# ST_LINK_V3E.net
KiCad netlist of a schematic drawn in Altium Designer
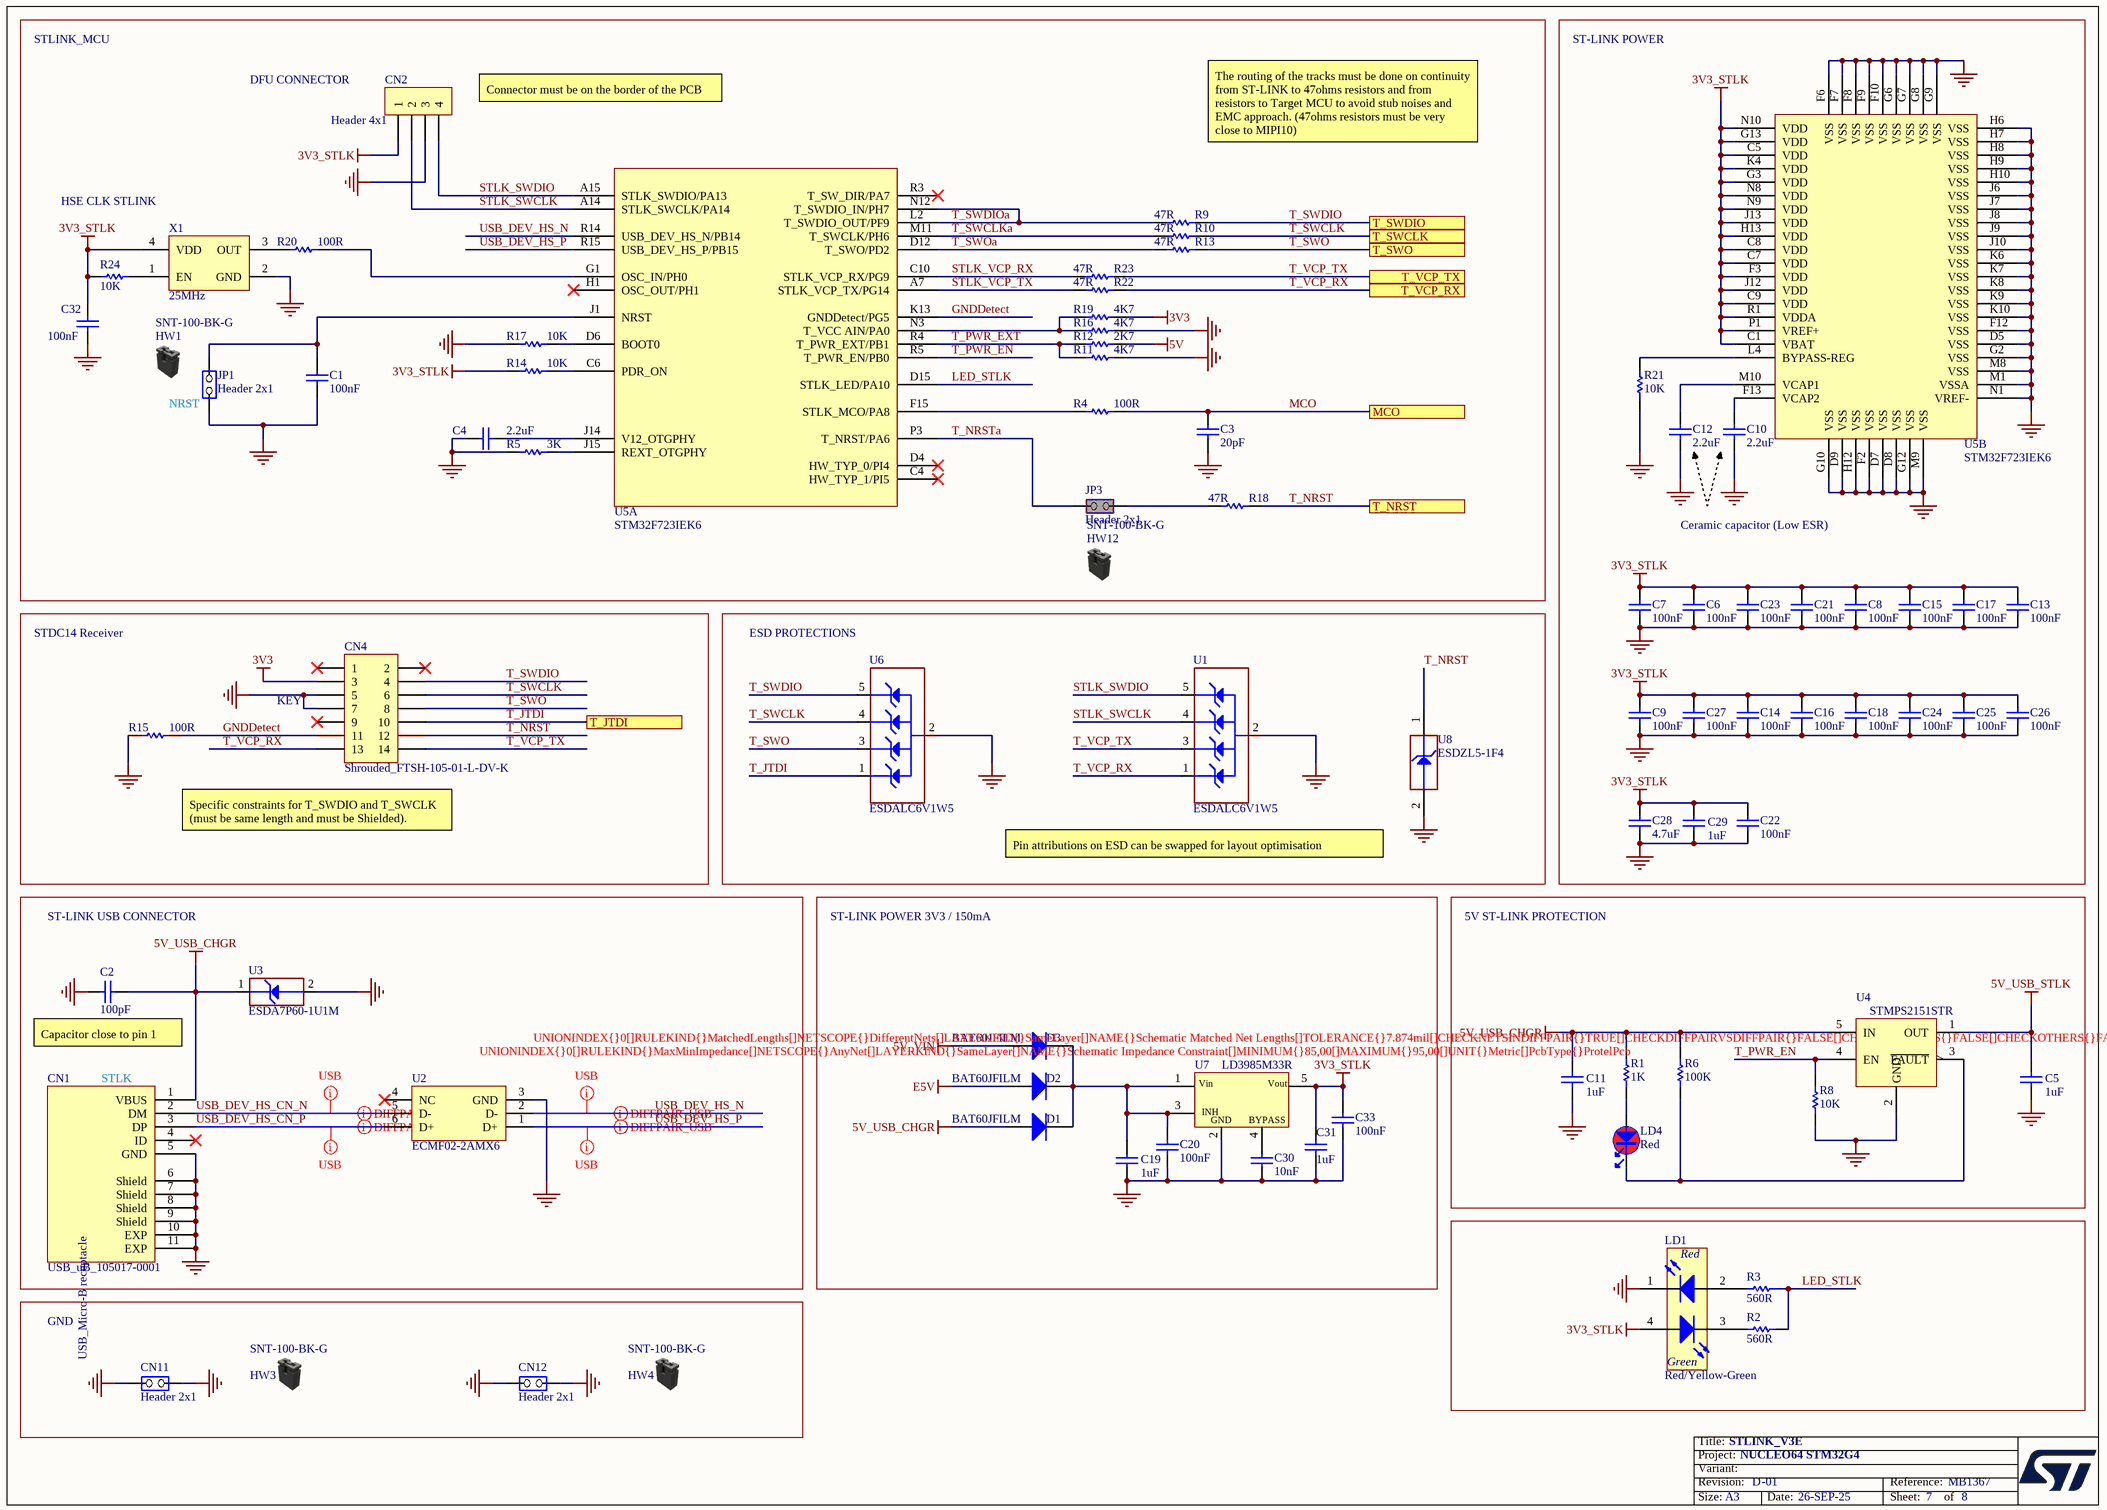
[diagram p0: ST_LINK_V3E.SchDoc]

(export (version "E")
  (design (tool "Eeschema 10.0.6"))
  (components
    (comp (ref "C1")
      (value "100nF")
      (footprint "C0402")
      (description "Capacitor, MLCC, 100nF, 16V, X7R, +/-10%, 0402, T=0.5mm")
      (fields
        (field (name "INTERNAL_PART_NUMBER") "MCD-00006")
        (field (name "MANUFACTURER_PART_NUMBER") "CC0402KRX7R7BB104")
      )
      (libsource (lib "MCD_PARTS_database") (part "Capacitor"))
    )
    (comp (ref "C2")
      (value "100pF")
      (footprint "C0402")
      (description "Capacitor, MLCC, 100pF, 50V, NPO, 5%, 0402, T=0,5mm")
      (fields
        (field (name "INTERNAL_PART_NUMBER") "MCD-00205")
        (field (name "MANUFACTURER_PART_NUMBER") "CC0402JRNPO9BN101")
      )
      (libsource (lib "MCD_PARTS_database") (part "Capacitor"))
    )
    (comp (ref "C3")
      (value "20pF")
      (footprint "C0402")
      (description "Capacitor, MLCC, 20pF, 50V, NPO, 5%, 0402, T=0,5mm")
      (fields
        (field (name "INTERNAL_PART_NUMBER") "MCD-00016")
        (field (name "MANUFACTURER_PART_NUMBER") "CC0402JRNPO9BN200")
      )
      (libsource (lib "MCD_PARTS_database") (part "Capacitor"))
    )
    (comp (ref "C4")
      (value "2.2uF")
      (footprint "C0603")
      (description "Capacitor, MLCC, 2.2uF, 10V, X5R, 10%, 0603, T=0,8mm")
      (fields
        (field (name "INTERNAL_PART_NUMBER") "MCD-00012")
        (field (name "MANUFACTURER_PART_NUMBER") "CC0603KRX5R6BB225")
      )
      (libsource (lib "MCD_PARTS_database") (part "Capacitor"))
    )
    (comp (ref "C5")
      (value "1uF")
      (footprint "C0603")
      (description "Capacitor, MLCC, 1uF, 16V, X5R, 10%, 0603, T=0,8mm")
      (fields
        (field (name "INTERNAL_PART_NUMBER") "MCD-00010")
        (field (name "MANUFACTURER_PART_NUMBER") "CC0603KRX5R7BB105")
      )
      (libsource (lib "MCD_PARTS_database") (part "Capacitor"))
    )
    (comp (ref "C6")
      (value "100nF")
      (footprint "C0402")
      (description "Capacitor, MLCC, 100nF, 16V, X7R, +/-10%, 0402, T=0.5mm")
      (fields
        (field (name "INTERNAL_PART_NUMBER") "MCD-00006")
        (field (name "MANUFACTURER_PART_NUMBER") "CC0402KRX7R7BB104")
      )
      (libsource (lib "MCD_PARTS_database") (part "Capacitor"))
    )
    (comp (ref "C7")
      (value "100nF")
      (footprint "C0402")
      (description "Capacitor, MLCC, 100nF, 16V, X7R, +/-10%, 0402, T=0.5mm")
      (fields
        (field (name "INTERNAL_PART_NUMBER") "MCD-00006")
        (field (name "MANUFACTURER_PART_NUMBER") "CC0402KRX7R7BB104")
      )
      (libsource (lib "MCD_PARTS_database") (part "Capacitor"))
    )
    (comp (ref "C8")
      (value "100nF")
      (footprint "C0402")
      (description "Capacitor, MLCC, 100nF, 16V, X7R, +/-10%, 0402, T=0.5mm")
      (fields
        (field (name "INTERNAL_PART_NUMBER") "MCD-00006")
        (field (name "MANUFACTURER_PART_NUMBER") "CC0402KRX7R7BB104")
      )
      (libsource (lib "MCD_PARTS_database") (part "Capacitor"))
    )
    (comp (ref "C9")
      (value "100nF")
      (footprint "C0402")
      (description "Capacitor, MLCC, 100nF, 16V, X7R, +/-10%, 0402, T=0.5mm")
      (fields
        (field (name "INTERNAL_PART_NUMBER") "MCD-00006")
        (field (name "MANUFACTURER_PART_NUMBER") "CC0402KRX7R7BB104")
      )
      (libsource (lib "MCD_PARTS_database") (part "Capacitor"))
    )
    (comp (ref "C10")
      (value "2.2uF")
      (footprint "C1206_H1P15")
      (description "Capacitor, MLCC, 2.2uF, 16V, X7R, 10%, 1206, T=1,15mm")
      (fields
        (field (name "INTERNAL_PART_NUMBER") "MCD-00008")
        (field (name "MANUFACTURER_PART_NUMBER") "CC1206KKX7R7BB225")
      )
      (libsource (lib "MCD_PARTS_database") (part "Capacitor"))
    )
    (comp (ref "C11")
      (value "1uF")
      (footprint "C0603")
      (description "Capacitor, MLCC, 1uF, 16V, X5R, 10%, 0603, T=0,8mm")
      (fields
        (field (name "INTERNAL_PART_NUMBER") "MCD-00010")
        (field (name "MANUFACTURER_PART_NUMBER") "CC0603KRX5R7BB105")
      )
      (libsource (lib "MCD_PARTS_database") (part "Capacitor"))
    )
    (comp (ref "C12")
      (value "2.2uF")
      (footprint "C1206_H1P15")
      (description "Capacitor, MLCC, 2.2uF, 16V, X7R, 10%, 1206, T=1,15mm")
      (fields
        (field (name "INTERNAL_PART_NUMBER") "MCD-00008")
        (field (name "MANUFACTURER_PART_NUMBER") "CC1206KKX7R7BB225")
      )
      (libsource (lib "MCD_PARTS_database") (part "Capacitor"))
    )
    (comp (ref "C13")
      (value "100nF")
      (footprint "C0402")
      (description "Capacitor, MLCC, 100nF, 16V, X7R, +/-10%, 0402, T=0.5mm")
      (fields
        (field (name "INTERNAL_PART_NUMBER") "MCD-00006")
        (field (name "MANUFACTURER_PART_NUMBER") "CC0402KRX7R7BB104")
      )
      (libsource (lib "MCD_PARTS_database") (part "Capacitor"))
    )
    (comp (ref "C14")
      (value "100nF")
      (footprint "C0402")
      (description "Capacitor, MLCC, 100nF, 16V, X7R, +/-10%, 0402, T=0.5mm")
      (fields
        (field (name "INTERNAL_PART_NUMBER") "MCD-00006")
        (field (name "MANUFACTURER_PART_NUMBER") "CC0402KRX7R7BB104")
      )
      (libsource (lib "MCD_PARTS_database") (part "Capacitor"))
    )
    (comp (ref "C15")
      (value "100nF")
      (footprint "C0402")
      (description "Capacitor, MLCC, 100nF, 16V, X7R, +/-10%, 0402, T=0.5mm")
      (fields
        (field (name "INTERNAL_PART_NUMBER") "MCD-00006")
        (field (name "MANUFACTURER_PART_NUMBER") "CC0402KRX7R7BB104")
      )
      (libsource (lib "MCD_PARTS_database") (part "Capacitor"))
    )
    (comp (ref "C16")
      (value "100nF")
      (footprint "C0402")
      (description "Capacitor, MLCC, 100nF, 16V, X7R, +/-10%, 0402, T=0.5mm")
      (fields
        (field (name "INTERNAL_PART_NUMBER") "MCD-00006")
        (field (name "MANUFACTURER_PART_NUMBER") "CC0402KRX7R7BB104")
      )
      (libsource (lib "MCD_PARTS_database") (part "Capacitor"))
    )
    (comp (ref "C17")
      (value "100nF")
      (footprint "C0402")
      (description "Capacitor, MLCC, 100nF, 16V, X7R, +/-10%, 0402, T=0.5mm")
      (fields
        (field (name "INTERNAL_PART_NUMBER") "MCD-00006")
        (field (name "MANUFACTURER_PART_NUMBER") "CC0402KRX7R7BB104")
      )
      (libsource (lib "MCD_PARTS_database") (part "Capacitor"))
    )
    (comp (ref "C18")
      (value "100nF")
      (footprint "C0402")
      (description "Capacitor, MLCC, 100nF, 16V, X7R, +/-10%, 0402, T=0.5mm")
      (fields
        (field (name "INTERNAL_PART_NUMBER") "MCD-00006")
        (field (name "MANUFACTURER_PART_NUMBER") "CC0402KRX7R7BB104")
      )
      (libsource (lib "MCD_PARTS_database") (part "Capacitor"))
    )
    (comp (ref "C19")
      (value "1uF")
      (footprint "C0603")
      (description "Capacitor, MLCC, 1uF, 16V, X5R, 10%, 0603, T=0,8mm")
      (fields
        (field (name "INTERNAL_PART_NUMBER") "MCD-00010")
        (field (name "MANUFACTURER_PART_NUMBER") "CC0603KRX5R7BB105")
      )
      (libsource (lib "MCD_PARTS_database") (part "Capacitor"))
    )
    (comp (ref "C20")
      (value "100nF")
      (footprint "C0402")
      (description "Capacitor, MLCC, 100nF, 16V, X7R, +/-10%, 0402, T=0.5mm")
      (fields
        (field (name "INTERNAL_PART_NUMBER") "MCD-00006")
        (field (name "MANUFACTURER_PART_NUMBER") "CC0402KRX7R7BB104")
      )
      (libsource (lib "MCD_PARTS_database") (part "Capacitor"))
    )
    (comp (ref "C21")
      (value "100nF")
      (footprint "C0402")
      (description "Capacitor, MLCC, 100nF, 16V, X7R, +/-10%, 0402, T=0.5mm")
      (fields
        (field (name "INTERNAL_PART_NUMBER") "MCD-00006")
        (field (name "MANUFACTURER_PART_NUMBER") "CC0402KRX7R7BB104")
      )
      (libsource (lib "MCD_PARTS_database") (part "Capacitor"))
    )
    (comp (ref "C22")
      (value "100nF")
      (footprint "C0402")
      (description "Capacitor, MLCC, 100nF, 16V, X7R, +/-10%, 0402, T=0.5mm")
      (fields
        (field (name "INTERNAL_PART_NUMBER") "MCD-00006")
        (field (name "MANUFACTURER_PART_NUMBER") "CC0402KRX7R7BB104")
      )
      (libsource (lib "MCD_PARTS_database") (part "Capacitor"))
    )
    (comp (ref "C23")
      (value "100nF")
      (footprint "C0402")
      (description "Capacitor, MLCC, 100nF, 16V, X7R, +/-10%, 0402, T=0.5mm")
      (fields
        (field (name "INTERNAL_PART_NUMBER") "MCD-00006")
        (field (name "MANUFACTURER_PART_NUMBER") "CC0402KRX7R7BB104")
      )
      (libsource (lib "MCD_PARTS_database") (part "Capacitor"))
    )
    (comp (ref "C24")
      (value "100nF")
      (footprint "C0402")
      (description "Capacitor, MLCC, 100nF, 16V, X7R, +/-10%, 0402, T=0.5mm")
      (fields
        (field (name "INTERNAL_PART_NUMBER") "MCD-00006")
        (field (name "MANUFACTURER_PART_NUMBER") "CC0402KRX7R7BB104")
      )
      (libsource (lib "MCD_PARTS_database") (part "Capacitor"))
    )
    (comp (ref "C25")
      (value "100nF")
      (footprint "C0402")
      (description "Capacitor, MLCC, 100nF, 16V, X7R, +/-10%, 0402, T=0.5mm")
      (fields
        (field (name "INTERNAL_PART_NUMBER") "MCD-00006")
        (field (name "MANUFACTURER_PART_NUMBER") "CC0402KRX7R7BB104")
      )
      (libsource (lib "MCD_PARTS_database") (part "Capacitor"))
    )
    (comp (ref "C26")
      (value "100nF")
      (footprint "C0402")
      (description "Capacitor, MLCC, 100nF, 16V, X7R, +/-10%, 0402, T=0.5mm")
      (fields
        (field (name "INTERNAL_PART_NUMBER") "MCD-00006")
        (field (name "MANUFACTURER_PART_NUMBER") "CC0402KRX7R7BB104")
      )
      (libsource (lib "MCD_PARTS_database") (part "Capacitor"))
    )
    (comp (ref "C27")
      (value "100nF")
      (footprint "C0402")
      (description "Capacitor, MLCC, 100nF, 16V, X7R, +/-10%, 0402, T=0.5mm")
      (fields
        (field (name "INTERNAL_PART_NUMBER") "MCD-00006")
        (field (name "MANUFACTURER_PART_NUMBER") "CC0402KRX7R7BB104")
      )
      (libsource (lib "MCD_PARTS_database") (part "Capacitor"))
    )
    (comp (ref "C28")
      (value "4.7uF")
      (footprint "C0603")
      (description "Capacitor, MLCC, 4.7uF, 16V, X5R, 10%, 0603, T=0.8mm")
      (fields
        (field (name "INTERNAL_PART_NUMBER") "MCD-00009")
        (field (name "MANUFACTURER_PART_NUMBER") "CC0603KRX5R7BB475")
      )
      (libsource (lib "MCD_PARTS_database") (part "Capacitor"))
    )
    (comp (ref "C29")
      (value "1uF")
      (footprint "C0603")
      (description "Capacitor, MLCC, 1uF, 16V, X5R, 10%, 0603, T=0,8mm")
      (fields
        (field (name "INTERNAL_PART_NUMBER") "MCD-00010")
        (field (name "MANUFACTURER_PART_NUMBER") "CC0603KRX5R7BB105")
      )
      (libsource (lib "MCD_PARTS_database") (part "Capacitor"))
    )
    (comp (ref "C30")
      (value "10nF")
      (footprint "C0402")
      (description "Capacitor, MLCC, 10nF, 16V, X7R, 10%, 0402, T=0.5mm")
      (fields
        (field (name "INTERNAL_PART_NUMBER") "MCD-00011")
        (field (name "MANUFACTURER_PART_NUMBER") "CC0402KRX7R7BB103")
      )
      (libsource (lib "MCD_PARTS_database") (part "Capacitor"))
    )
    (comp (ref "C31")
      (value "1uF")
      (footprint "C0603")
      (description "Capacitor, MLCC, 1uF, 16V, X5R, 10%, 0603, T=0,8mm")
      (fields
        (field (name "INTERNAL_PART_NUMBER") "MCD-00010")
        (field (name "MANUFACTURER_PART_NUMBER") "CC0603KRX5R7BB105")
      )
      (libsource (lib "MCD_PARTS_database") (part "Capacitor"))
    )
    (comp (ref "C32")
      (value "100nF")
      (footprint "C0402")
      (description "Capacitor, MLCC, 100nF, 16V, X7R, +/-10%, 0402, T=0.5mm")
      (fields
        (field (name "INTERNAL_PART_NUMBER") "MCD-00006")
        (field (name "MANUFACTURER_PART_NUMBER") "CC0402KRX7R7BB104")
      )
      (libsource (lib "MCD_PARTS_database") (part "Capacitor"))
    )
    (comp (ref "C33")
      (value "100nF")
      (footprint "C0402")
      (description "Capacitor, MLCC, 100nF, 16V, X7R, +/-10%, 0402, T=0.5mm")
      (fields
        (field (name "INTERNAL_PART_NUMBER") "MCD-00006")
        (field (name "MANUFACTURER_PART_NUMBER") "CC0402KRX7R7BB104")
      )
      (libsource (lib "MCD_PARTS_database") (part "Capacitor"))
    )
    (comp (ref "CN1")
      (value "USB_uB_105017-0001")
      (footprint "CON_USBMICROB_MOLEX_105017-0001_H2P90")
      (description "USB-MICRO-B, 0.65mm, RA, SMT, Bottom Mount,")
      (fields
        (field (name "INTERNAL_PART_NUMBER") "MCD-00028")
        (field (name "MANUFACTURER_PART_NUMBER") "1050170001")
      )
      (libsource (lib "MCD_PARTS_database") (part "USB_uB_105017.0001"))
    )
    (comp (ref "CN2")
      (value "Header 4x1")
      (footprint "CON_SAMTEC_TSW-104-07-G-S")
      (description "Header, 4x1, 2,54mm, VR, TH, Height 5.84mm/2.54mm")
      (fields
        (field (name "INTERNAL_PART_NUMBER") "MCD-00029")
        (field (name "MANUFACTURER_PART_NUMBER") "TSW-104-07-G-S")
      )
      (libsource (lib "MCD_PARTS_database") (part "Header 4x1"))
    )
    (comp (ref "CN4")
      (value "Shrouded_FTSH-105-01-L-DV-K")
      (footprint "CON_STDC14_Receiver_MEDIUM_WITH_MIPI10_3D")
      (fields
        (field (name "INTERNAL_PART_NUMBER") "MCD-01226")
        (field (name "MANUFACTURER_PART_NUMBER") "FTSH-105-01-L-DV-K")
        (field (name "MANUFACTURER") "SAMTEC")
      )
      (libsource (lib "MCD_PARTS_database") (part "Header 7x2"))
    )
    (comp (ref "CN11")
      (value "Header 2x1")
      (footprint "CON_SAMTEC_TSW-102-09-X-S")
      (description "Header, 2x1, 2,54mm, VR, TH, Height 5.84mm/10.16mm")
      (fields
        (field (name "INTERNAL_PART_NUMBER") "MCD-00214")
        (field (name "MANUFACTURER_PART_NUMBER") "TSW-102-09-G-S")
      )
      (libsource (lib "MCD_PARTS_database") (part "Jumper_Header 2x1"))
    )
    (comp (ref "CN12")
      (value "Header 2x1")
      (footprint "CON_SAMTEC_TSW-102-09-X-S")
      (description "Header, 2x1, 2,54mm, VR, TH, Height 5.84mm/10.16mm")
      (fields
        (field (name "INTERNAL_PART_NUMBER") "MCD-00214")
        (field (name "MANUFACTURER_PART_NUMBER") "TSW-102-09-G-S")
      )
      (libsource (lib "MCD_PARTS_database") (part "Jumper_Header 2x1"))
    )
    (comp (ref "D1")
      (value "BAT60JFILM")
      (footprint "DIO_SOD323")
      (fields
        (field (name "INTERNAL_PART_NUMBER") "MCD-00034")
        (field (name "MANUFACTURER") "STMICROELECTRONICS")
        (field (name "BMS_PART_NUMBER") "9151097")
      )
      (libsource (lib "MCD_PARTS_database") (part "BAT60JFILM"))
    )
    (comp (ref "D2")
      (value "BAT60JFILM")
      (footprint "DIO_SOD323")
      (fields
        (field (name "INTERNAL_PART_NUMBER") "MCD-00034")
        (field (name "MANUFACTURER") "STMICROELECTRONICS")
        (field (name "BMS_PART_NUMBER") "9151097")
      )
      (libsource (lib "MCD_PARTS_database") (part "BAT60JFILM"))
    )
    (comp (ref "D3")
      (value "BAT60JFILM")
      (footprint "DIO_SOD323")
      (fields
        (field (name "INTERNAL_PART_NUMBER") "MCD-00034")
        (field (name "MANUFACTURER") "STMICROELECTRONICS")
        (field (name "BMS_PART_NUMBER") "9151097")
      )
      (libsource (lib "MCD_PARTS_database") (part "BAT60JFILM"))
    )
    (comp (ref "HW1")
      (value "SNT-100-BK-G")
      (description "SHUNT 2.54mm BLACK")
      (fields (field (name "INTERNAL_PART_NUMBER") "MCD-00043") (field (name "MANUFACTURER") "SAMTEC"))
      (libsource (lib "MCD_PARTS_database") (part "Shunt Black 2.54mm"))
    )
    (comp (ref "HW3")
      (value "SNT-100-BK-G")
      (description "SHUNT 2.54mm BLACK")
      (fields (field (name "INTERNAL_PART_NUMBER") "MCD-00043") (field (name "MANUFACTURER") "SAMTEC"))
      (libsource (lib "MCD_PARTS_database") (part "Shunt Black 2.54mm"))
    )
    (comp (ref "HW4")
      (value "SNT-100-BK-G")
      (description "SHUNT 2.54mm BLACK")
      (fields (field (name "INTERNAL_PART_NUMBER") "MCD-00043") (field (name "MANUFACTURER") "SAMTEC"))
      (libsource (lib "MCD_PARTS_database") (part "Shunt Black 2.54mm"))
    )
    (comp (ref "HW12")
      (value "SNT-100-BK-G")
      (description "SHUNT 2.54mm BLACK")
      (fields (field (name "INTERNAL_PART_NUMBER") "MCD-00043") (field (name "MANUFACTURER") "SAMTEC"))
      (libsource (lib "MCD_PARTS_database") (part "Shunt Black 2.54mm"))
    )
    (comp (ref "JP1")
      (value "Header 2x1")
      (footprint "CON_SAMTEC_TSW-102-07-G-S")
      (description "Header, 2x1, 2,54mm, VR, TH, Height 5.84mm/2.54mm")
      (fields
        (field (name "INTERNAL_PART_NUMBER") "MCD-00045")
        (field (name "MANUFACTURER_PART_NUMBER") "TSW-102-07-G-S")
      )
      (libsource (lib "MCD_PARTS_database") (part "Jumper_Header 2x1"))
    )
    (comp (ref "JP3")
      (value "Header 2x1")
      (footprint "CON_SAMTEC_TSW-102-07-G-S")
      (description "Header, 2x1, 2,54mm, VR, TH, Height 5.84mm/2.54mm - Shunt Fitted by default")
      (fields
        (field (name "INTERNAL_PART_NUMBER") "MCD-00683")
        (field (name "MANUFACTURER_PART_NUMBER") "TSW-102-07-G-S")
      )
      (libsource (lib "MCD_PARTS_database") (part "Jumper_Header 2x1 Fitted"))
    )
    (comp (ref "LD1")
      (value "Red/Yellow-Green")
      (footprint "LED_BI-GR_HSMF-A201-A00J1")
      (description "LED Bicolor")
      (fields (field (name "INTERNAL_PART_NUMBER") "MCD-02402") (field (name "MANUFACTURER") "EVERLIGHT"))
      (libsource (lib "MCD_PARTS_database") (part "LD_BICOLOR_CMS"))
    )
    (comp (ref "LD4")
      (value "Red")
      (footprint "LED_0603_VISHAY_VLMS1300-GS08_RED_1A2K_H0P8")
      (description "LED, Red, 1V7 to 2V2, 5mA, 0603")
      (fields (field (name "INTERNAL_PART_NUMBER") "MCD-02787") (field (name "MANUFACTURER") "EVERLIGHT"))
      (libsource (lib "MCD_PARTS_database") (part "LED_red"))
    )
    (comp (ref "R1")
      (value "1K")
      (footprint "R0603")
      (description "Resistor,1K,0603,1%,1/10W")
      (fields
        (field (name "INTERNAL_PART_NUMBER") "MCD-00070")
        (field (name "MANUFACTURER_PART_NUMBER") "RC0603FR-071KL")
      )
      (libsource (lib "MCD_PARTS_database") (part "Resistor"))
    )
    (comp (ref "R2")
      (value "560R")
      (footprint "R0603")
      (description "Resistor, 560R, 0603, +/-1%, 1/10W")
      (fields
        (field (name "INTERNAL_PART_NUMBER") "MCD-00490")
        (field (name "MANUFACTURER_PART_NUMBER") "RC0603FR-07560RL")
      )
      (libsource (lib "MCD_PARTS_database") (part "Resistor"))
    )
    (comp (ref "R3")
      (value "560R")
      (footprint "R0603")
      (description "Resistor, 560R, 0603, +/-1%, 1/10W")
      (fields
        (field (name "INTERNAL_PART_NUMBER") "MCD-00490")
        (field (name "MANUFACTURER_PART_NUMBER") "RC0603FR-07560RL")
      )
      (libsource (lib "MCD_PARTS_database") (part "Resistor"))
    )
    (comp (ref "R4")
      (value "100R")
      (footprint "R0402")
      (description "Resistor, 100R, 0402, +/- 1%, 1/16W")
      (fields
        (field (name "INTERNAL_PART_NUMBER") "MCD-00067")
        (field (name "MANUFACTURER_PART_NUMBER") "RC0402FR-07100RL")
      )
      (libsource (lib "MCD_PARTS_database") (part "Resistor"))
    )
    (comp (ref "R5")
      (value "3K")
      (footprint "R0402")
      (description "Resistor,3K,0402,1%,1/16W")
      (fields
        (field (name "INTERNAL_PART_NUMBER") "MCD-00185")
        (field (name "MANUFACTURER_PART_NUMBER") "RC0402FR-073KL")
      )
      (libsource (lib "MCD_PARTS_database") (part "Resistor"))
    )
    (comp (ref "R6")
      (value "100K")
      (footprint "R0603")
      (description "Resistor,100K,0603,1%,1/10W")
      (fields
        (field (name "INTERNAL_PART_NUMBER") "MCD-00223")
        (field (name "MANUFACTURER_PART_NUMBER") "RC0603FR-07100KL")
      )
      (libsource (lib "MCD_PARTS_database") (part "Resistor"))
    )
    (comp (ref "R8")
      (value "10K")
      (footprint "R0603")
      (description "Resistor,10K,0603,1%,1/10W")
      (fields
        (field (name "INTERNAL_PART_NUMBER") "MCD-00220")
        (field (name "MANUFACTURER_PART_NUMBER") "RC0603FR-0710KL")
      )
      (libsource (lib "MCD_PARTS_database") (part "Resistor"))
    )
    (comp (ref "R9")
      (value "47R")
      (footprint "R0402")
      (description "Resistor,47R,0402,1%,1/16W")
      (fields
        (field (name "INTERNAL_PART_NUMBER") "MCD-00481")
        (field (name "MANUFACTURER_PART_NUMBER") "RC0402FR-0747RL")
      )
      (libsource (lib "MCD_PARTS_database") (part "Resistor"))
    )
    (comp (ref "R10")
      (value "47R")
      (footprint "R0402")
      (description "Resistor,47R,0402,1%,1/16W")
      (fields
        (field (name "INTERNAL_PART_NUMBER") "MCD-00481")
        (field (name "MANUFACTURER_PART_NUMBER") "RC0402FR-0747RL")
      )
      (libsource (lib "MCD_PARTS_database") (part "Resistor"))
    )
    (comp (ref "R11")
      (value "4K7")
      (footprint "R0402")
      (description "Resistor,4K7,0402,1%,1/16W")
      (fields
        (field (name "INTERNAL_PART_NUMBER") "MCD-00065")
        (field (name "MANUFACTURER_PART_NUMBER") "RC0402FR-074K7L")
      )
      (libsource (lib "MCD_PARTS_database") (part "Resistor"))
    )
    (comp (ref "R12")
      (value "2K7")
      (footprint "R0402")
      (description "Resistor,2K7,0402,1%,1/16W")
      (fields
        (field (name "INTERNAL_PART_NUMBER") "MCD-00055")
        (field (name "MANUFACTURER_PART_NUMBER") "RC0402FR-072K7L")
      )
      (libsource (lib "MCD_PARTS_database") (part "Resistor"))
    )
    (comp (ref "R13")
      (value "47R")
      (footprint "R0402")
      (description "Resistor,47R,0402,1%,1/16W")
      (fields
        (field (name "INTERNAL_PART_NUMBER") "MCD-00481")
        (field (name "MANUFACTURER_PART_NUMBER") "RC0402FR-0747RL")
      )
      (libsource (lib "MCD_PARTS_database") (part "Resistor"))
    )
    (comp (ref "R14")
      (value "10K")
      (footprint "R0402")
      (description "Resistor,10K,0402,1%,1/16W")
      (fields
        (field (name "INTERNAL_PART_NUMBER") "MCD-00053")
        (field (name "MANUFACTURER_PART_NUMBER") "RC0402FR-0710KL")
      )
      (libsource (lib "MCD_PARTS_database") (part "Resistor"))
    )
    (comp (ref "R15")
      (value "100R")
      (footprint "R0402")
      (description "Resistor, 100R, 0402, +/- 1%, 1/16W")
      (fields
        (field (name "INTERNAL_PART_NUMBER") "MCD-00067")
        (field (name "MANUFACTURER_PART_NUMBER") "RC0402FR-07100RL")
      )
      (libsource (lib "MCD_PARTS_database") (part "Resistor"))
    )
    (comp (ref "R16")
      (value "4K7")
      (footprint "R0402")
      (description "Resistor,4K7,0402,1%,1/16W")
      (fields
        (field (name "INTERNAL_PART_NUMBER") "MCD-00065")
        (field (name "MANUFACTURER_PART_NUMBER") "RC0402FR-074K7L")
      )
      (libsource (lib "MCD_PARTS_database") (part "Resistor"))
    )
    (comp (ref "R17")
      (value "10K")
      (footprint "R0402")
      (description "Resistor,10K,0402,1%,1/16W")
      (fields
        (field (name "INTERNAL_PART_NUMBER") "MCD-00053")
        (field (name "MANUFACTURER_PART_NUMBER") "RC0402FR-0710KL")
      )
      (libsource (lib "MCD_PARTS_database") (part "Resistor"))
    )
    (comp (ref "R18")
      (value "47R")
      (footprint "R0402")
      (description "Resistor,47R,0402,1%,1/16W")
      (fields
        (field (name "INTERNAL_PART_NUMBER") "MCD-00481")
        (field (name "MANUFACTURER_PART_NUMBER") "RC0402FR-0747RL")
      )
      (libsource (lib "MCD_PARTS_database") (part "Resistor"))
    )
    (comp (ref "R19")
      (value "4K7")
      (footprint "R0402")
      (description "Resistor,4K7,0402,1%,1/16W")
      (fields
        (field (name "INTERNAL_PART_NUMBER") "MCD-00065")
        (field (name "MANUFACTURER_PART_NUMBER") "RC0402FR-074K7L")
      )
      (libsource (lib "MCD_PARTS_database") (part "Resistor"))
    )
    (comp (ref "R20")
      (value "100R")
      (footprint "R0402")
      (description "Resistor, 100R, 0402, +/- 1%, 1/16W")
      (fields
        (field (name "INTERNAL_PART_NUMBER") "MCD-00067")
        (field (name "MANUFACTURER_PART_NUMBER") "RC0402FR-07100RL")
      )
      (libsource (lib "MCD_PARTS_database") (part "Resistor"))
    )
    (comp (ref "R21")
      (value "10K")
      (footprint "R0402")
      (description "Resistor,10K,0402,1%,1/16W")
      (fields
        (field (name "INTERNAL_PART_NUMBER") "MCD-00053")
        (field (name "MANUFACTURER_PART_NUMBER") "RC0402FR-0710KL")
      )
      (libsource (lib "MCD_PARTS_database") (part "Resistor"))
    )
    (comp (ref "R22")
      (value "47R")
      (footprint "R0402")
      (description "Resistor,47R,0402,1%,1/16W")
      (fields
        (field (name "INTERNAL_PART_NUMBER") "MCD-00481")
        (field (name "MANUFACTURER_PART_NUMBER") "RC0402FR-0747RL")
      )
      (libsource (lib "MCD_PARTS_database") (part "Resistor"))
    )
    (comp (ref "R23")
      (value "47R")
      (footprint "R0402")
      (description "Resistor,47R,0402,1%,1/16W")
      (fields
        (field (name "INTERNAL_PART_NUMBER") "MCD-00481")
        (field (name "MANUFACTURER_PART_NUMBER") "RC0402FR-0747RL")
      )
      (libsource (lib "MCD_PARTS_database") (part "Resistor"))
    )
    (comp (ref "R24")
      (value "10K")
      (footprint "R0402")
      (description "Resistor,10K,0402,1%,1/16W")
      (fields
        (field (name "INTERNAL_PART_NUMBER") "MCD-00053")
        (field (name "MANUFACTURER_PART_NUMBER") "RC0402FR-0710KL")
      )
      (libsource (lib "MCD_PARTS_database") (part "Resistor"))
    )
    (comp (ref "U1")
      (value "ESDALC6V1W5")
      (footprint "ESD_SOT323-5L")
      (description "Dual Transil array for ESD protection")
      (fields
        (field (name "INTERNAL_PART_NUMBER") "MCD-00136")
        (field (name "MANUFACTURER") "STMICROELECTRONICS")
      )
      (libsource (lib "MCD_PARTS_database") (part "ESDALC6V1W5"))
    )
    (comp (ref "U2")
      (value "ECMF02-2AMX6")
      (footprint "ESD_QFN-6L_1P7X1P5_P050")
      (description "Common mode filter with ESD protection for USB 2.0 interface")
      (fields
        (field (name "INTERNAL_PART_NUMBER") "MCD-00649")
        (field (name "MANUFACTURER") "STMICROELECTRONICS")
      )
      (libsource (lib "MCD_PARTS_database") (part "ECMF02-2AMX6"))
    )
    (comp (ref "U3")
      (value "ESDA7P60-1U1M")
      (footprint "ESD_QFN2_1P6X1_P125")
      (description "High power transient voltage suppressor, 7V breakdown")
      (fields
        (field (name "INTERNAL_PART_NUMBER") "MCD-00251")
        (field (name "MANUFACTURER") "STMICROELECTRONICS")
      )
      (libsource (lib "") (part "ESD-TRANSIL_1"))
    )
    (comp (ref "U4")
      (value "STMPS2151STR")
      (footprint "MOS_SOT23-5L")
      (description "500mA, Enhanced single channel power switches with active high enable pin")
      (fields
        (field (name "INTERNAL_PART_NUMBER") "MCD-00159")
        (field (name "MANUFACTURER") "STMICROELECTRONICS")
      )
      (libsource (lib "MCD_PARTS_database") (part "STMPS2151STR"))
    )
    (comp (ref "U5")
      (value "STM32F723IEK6")
      (footprint "ICC_UFBGA201_176+25_10X10_P065")
      (description "STM32F723IEK  (STM32F7) BGA176")
      (fields
        (field (name "INTERNAL_PART_NUMBER") "MCD-00596")
        (field (name "MANUFACTURER") "STMICROELECTRONICS")
      )
      (libsource (lib "MCD_PARTS_database") (part "ST-LINKV3E_SWD"))
    )
    (comp (ref "U6")
      (value "ESDALC6V1W5")
      (footprint "ESD_SOT323-5L")
      (description "Dual Transil array for ESD protection")
      (fields
        (field (name "INTERNAL_PART_NUMBER") "MCD-00136")
        (field (name "MANUFACTURER") "STMICROELECTRONICS")
      )
      (libsource (lib "MCD_PARTS_database") (part "ESDALC6V1W5"))
    )
    (comp (ref "U7")
      (value "LD3985M33R")
      (footprint "REG_SOT23-5L")
      (description "Ultra low drop-low noise BiCMOS voltage, regulators low ESR capacitors compatible")
      (fields
        (field (name "INTERNAL_PART_NUMBER") "MCD-00086")
        (field (name "MANUFACTURER") "STMICROELECTRONICS")
      )
      (libsource (lib "MCD_PARTS_database") (part "LD3985M33R"))
    )
    (comp (ref "U8")
      (value "ESDZL5-1F4")
      (footprint "ESD_0201_H0P3_1K_2A")
      (description "Diode, ESD TVS, 5V5, 100nA, 10V, 0201")
      (fields
        (field (name "INTERNAL_PART_NUMBER") "MCD-03501")
        (field (name "MANUFACTURER") "STMICROELECTRONICS")
      )
      (libsource (lib "MCD_PARTS_database") (part "ESD-TRANSIL"))
    )
    (comp (ref "X1")
      (value "25MHz")
      (footprint "OSC_NDK_NZ2520SB_4P")
      (description "Oscillator 25.00Mhz, -+50PPM, 3.3V, Temp -55 to +125°C")
      (fields
        (field (name "INTERNAL_PART_NUMBER") "MCD-00597")
        (field (name "MANUFACTURER_PART_NUMBER") "NZ2520SH-25MHz-END4869C")
      )
      (libsource (lib "MCD_PARTS_database") (part "Oscillator_4pins"))
    )
  )
  (nets
    (net (code "1") (name "/GNDDetect") (class "Default")
      (node (ref "CN4") (pin "11") (pinfunction "11_11") (pintype "passive"))
      (node (ref "R15") (pin "2") (pinfunction "2_2") (pintype "passive"))
      (node (ref "U5") (pin "K13") (pinfunction "GNDDetect/PG5_K13") (pintype "passive"))
    )
    (net (code "2") (name "/LED_STLK") (class "Default")
      (node (ref "R2") (pin "2") (pinfunction "2_2") (pintype "passive"))
      (node (ref "R3") (pin "2") (pinfunction "2_2") (pintype "passive"))
      (node (ref "U5") (pin "D15") (pinfunction "STLK_LED/PA10_D15") (pintype "passive"))
    )
    (net (code "3") (name "/MCO") (class "Default")
      (node (ref "C3") (pin "2") (pinfunction "2_2") (pintype "passive"))
      (node (ref "R4") (pin "2") (pinfunction "2_2") (pintype "passive"))
    )
    (net (code "4") (name "/STLK_SWCLK") (class "Default")
      (node (ref "CN2") (pin "2") (pinfunction "2_2") (pintype "passive"))
      (node (ref "U1") (pin "4") (pinfunction "IO3_4") (pintype "passive"))
      (node (ref "U5") (pin "A14") (pinfunction "STLK_SWCLK/PA14_A14") (pintype "passive"))
    )
    (net (code "5") (name "/STLK_SWDIO") (class "Default")
      (node (ref "CN2") (pin "4") (pinfunction "4_4") (pintype "passive"))
      (node (ref "U1") (pin "5") (pinfunction "IO4_5") (pintype "passive"))
      (node (ref "U5") (pin "A15") (pinfunction "STLK_SWDIO/PA13_A15") (pintype "passive"))
    )
    (net (code "6") (name "/STLK_VCP_RX") (class "Default")
      (node (ref "R23") (pin "1") (pinfunction "1_1") (pintype "passive"))
      (node (ref "U5") (pin "C10") (pinfunction "STLK_VCP_RX/PG9_C10") (pintype "passive"))
    )
    (net (code "7") (name "/STLK_VCP_TX") (class "Default")
      (node (ref "R22") (pin "1") (pinfunction "1_1") (pintype "passive"))
      (node (ref "U5") (pin "A7") (pinfunction "STLK_VCP_TX/PG14_A7") (pintype "passive"))
    )
    (net (code "8") (name "/T_JTDI") (class "Default")
      (node (ref "CN4") (pin "10") (pinfunction "10_10") (pintype "passive"))
      (node (ref "U6") (pin "1") (pinfunction "IO1_1") (pintype "passive"))
    )
    (net (code "9") (name "/T_NRST") (class "Default")
      (node (ref "CN4") (pin "12") (pinfunction "12_12") (pintype "passive"))
      (node (ref "R18") (pin "2") (pinfunction "2_2") (pintype "passive"))
      (node (ref "U8") (pin "1") (pinfunction "IO1_1") (pintype "passive"))
    )
    (net (code "10") (name "/T_NRSTa") (class "Default")
      (node (ref "JP3") (pin "1") (pinfunction "COMMON_1") (pintype "passive"))
      (node (ref "U5") (pin "P3") (pinfunction "T_NRST/PA6_P3") (pintype "passive"))
    )
    (net (code "11") (name "/T_PWR_EN") (class "Default")
      (node (ref "R8") (pin "1") (pinfunction "1_1") (pintype "passive"))
      (node (ref "U4") (pin "4") (pinfunction "EN_4") (pintype "passive"))
      (node (ref "U5") (pin "R5") (pinfunction "T_PWR_EN/PB0_R5") (pintype "passive"))
    )
    (net (code "12") (name "/T_PWR_EXT") (class "Default")
      (node (ref "R11") (pin "2") (pinfunction "2_2") (pintype "passive"))
      (node (ref "R12") (pin "2") (pinfunction "2_2") (pintype "passive"))
      (node (ref "U5") (pin "R4") (pinfunction "T_PWR_EXT/PB1_R4") (pintype "passive"))
    )
    (net (code "13") (name "/T_SWCLK") (class "Default")
      (node (ref "CN4") (pin "6") (pinfunction "6_6") (pintype "passive"))
      (node (ref "R10") (pin "2") (pinfunction "2_2") (pintype "passive"))
      (node (ref "U6") (pin "4") (pinfunction "IO3_4") (pintype "passive"))
    )
    (net (code "14") (name "/T_SWCLKa") (class "Default")
      (node (ref "R10") (pin "1") (pinfunction "1_1") (pintype "passive"))
      (node (ref "U5") (pin "M11") (pinfunction "T_SWCLK/PH6_M11") (pintype "passive"))
    )
    (net (code "15") (name "/T_SWDIO") (class "Default")
      (node (ref "CN4") (pin "4") (pinfunction "4_4") (pintype "passive"))
      (node (ref "R9") (pin "2") (pinfunction "2_2") (pintype "passive"))
      (node (ref "U6") (pin "5") (pinfunction "IO4_5") (pintype "passive"))
    )
    (net (code "16") (name "/T_SWDIOa") (class "Default")
      (node (ref "R9") (pin "1") (pinfunction "1_1") (pintype "passive"))
      (node (ref "U5") (pin "L2") (pinfunction "T_SWDIO_OUT/PF9_L2") (pintype "passive"))
      (node (ref "U5") (pin "N12") (pinfunction "T_SWDIO_IN/PH7_N12") (pintype "passive"))
    )
    (net (code "17") (name "/T_SWO") (class "Default")
      (node (ref "CN4") (pin "8") (pinfunction "8_8") (pintype "passive"))
      (node (ref "R13") (pin "2") (pinfunction "2_2") (pintype "passive"))
      (node (ref "U6") (pin "3") (pinfunction "IO2_3") (pintype "passive"))
    )
    (net (code "18") (name "/T_SWOa") (class "Default")
      (node (ref "R13") (pin "1") (pinfunction "1_1") (pintype "passive"))
      (node (ref "U5") (pin "D12") (pinfunction "T_SWO/PD2_D12") (pintype "passive"))
    )
    (net (code "19") (name "/T_VCP_RX") (class "Default")
      (node (ref "CN4") (pin "13") (pinfunction "13_13") (pintype "passive"))
      (node (ref "R22") (pin "2") (pinfunction "2_2") (pintype "passive"))
      (node (ref "U1") (pin "1") (pinfunction "IO1_1") (pintype "passive"))
    )
    (net (code "20") (name "/T_VCP_TX") (class "Default")
      (node (ref "CN4") (pin "14") (pinfunction "14_14") (pintype "passive"))
      (node (ref "R23") (pin "2") (pinfunction "2_2") (pintype "passive"))
      (node (ref "U1") (pin "3") (pinfunction "IO2_3") (pintype "passive"))
    )
    (net (code "21") (name "/USB_DEV_HS_CN_N") (class "Default")
      (node (ref "CN1") (pin "2") (pinfunction "DM_2") (pintype "passive"))
      (node (ref "U2") (pin "5") (pinfunction "D-_5") (pintype "passive"))
    )
    (net (code "22") (name "/USB_DEV_HS_CN_P") (class "Default")
      (node (ref "CN1") (pin "3") (pinfunction "DP_3") (pintype "passive"))
      (node (ref "U2") (pin "6") (pinfunction "D+_6") (pintype "passive"))
    )
    (net (code "23") (name "/USB_DEV_HS_N") (class "Default")
      (node (ref "U2") (pin "2") (pinfunction "D-_2") (pintype "passive"))
      (node (ref "U5") (pin "R14") (pinfunction "USB_DEV_HS_N/PB14_R14") (pintype "passive"))
    )
    (net (code "24") (name "/USB_DEV_HS_P") (class "Default")
      (node (ref "U2") (pin "1") (pinfunction "D+_1") (pintype "passive"))
      (node (ref "U5") (pin "R15") (pinfunction "USB_DEV_HS_P/PB15_R15") (pintype "passive"))
    )
    (net (code "25") (name "3V3") (class "Default")
      (node (ref "CN4") (pin "3") (pinfunction "3_3") (pintype "passive"))
      (node (ref "R19") (pin "2") (pinfunction "2_2") (pintype "passive"))
    )
    (net (code "26") (name "3V3_STLK") (class "Default")
      (node (ref "C13") (pin "2") (pinfunction "2_2") (pintype "passive"))
      (node (ref "C14") (pin "2") (pinfunction "2_2") (pintype "passive"))
      (node (ref "C15") (pin "2") (pinfunction "2_2") (pintype "passive"))
      (node (ref "C16") (pin "2") (pinfunction "2_2") (pintype "passive"))
      (node (ref "C17") (pin "2") (pinfunction "2_2") (pintype "passive"))
      (node (ref "C18") (pin "2") (pinfunction "2_2") (pintype "passive"))
      (node (ref "C21") (pin "2") (pinfunction "2_2") (pintype "passive"))
      (node (ref "C22") (pin "2") (pinfunction "2_2") (pintype "passive"))
      (node (ref "C23") (pin "2") (pinfunction "2_2") (pintype "passive"))
      (node (ref "C24") (pin "2") (pinfunction "2_2") (pintype "passive"))
      (node (ref "C25") (pin "2") (pinfunction "2_2") (pintype "passive"))
      (node (ref "C26") (pin "2") (pinfunction "2_2") (pintype "passive"))
      (node (ref "C27") (pin "2") (pinfunction "2_2") (pintype "passive"))
      (node (ref "C28") (pin "2") (pinfunction "2_2") (pintype "passive"))
      (node (ref "C29") (pin "2") (pinfunction "2_2") (pintype "passive"))
      (node (ref "C31") (pin "2") (pinfunction "2_2") (pintype "passive"))
      (node (ref "C32") (pin "2") (pinfunction "2_2") (pintype "passive"))
      (node (ref "C33") (pin "2") (pinfunction "2_2") (pintype "passive"))
      (node (ref "C6") (pin "2") (pinfunction "2_2") (pintype "passive"))
      (node (ref "C7") (pin "2") (pinfunction "2_2") (pintype "passive"))
      (node (ref "C8") (pin "2") (pinfunction "2_2") (pintype "passive"))
      (node (ref "C9") (pin "2") (pinfunction "2_2") (pintype "passive"))
      (node (ref "CN2") (pin "1") (pinfunction "1_1") (pintype "passive"))
      (node (ref "LD1") (pin "4") (pinfunction "YellowGreen_anode_4") (pintype "passive"))
      (node (ref "R14") (pin "1") (pinfunction "1_1") (pintype "passive"))
      (node (ref "R24") (pin "1") (pinfunction "1_1") (pintype "passive"))
      (node (ref "U5") (pin "C1") (pinfunction "VBAT_C1") (pintype "passive"))
      (node (ref "U5") (pin "C5") (pinfunction "VDD_C5") (pintype "passive"))
      (node (ref "U5") (pin "C7") (pinfunction "VDD_C7") (pintype "passive"))
      (node (ref "U5") (pin "C8") (pinfunction "VDD_C8") (pintype "passive"))
      (node (ref "U5") (pin "C9") (pinfunction "VDD_C9") (pintype "passive"))
      (node (ref "U5") (pin "F3") (pinfunction "VDD_F3") (pintype "passive"))
      (node (ref "U5") (pin "G13") (pinfunction "VDD_G13") (pintype "passive"))
      (node (ref "U5") (pin "G3") (pinfunction "VDD_G3") (pintype "passive"))
      (node (ref "U5") (pin "H13") (pinfunction "VDD_H13") (pintype "passive"))
      (node (ref "U5") (pin "J12") (pinfunction "VDD_J12") (pintype "passive"))
      (node (ref "U5") (pin "J13") (pinfunction "VDD_J13") (pintype "passive"))
      (node (ref "U5") (pin "K4") (pinfunction "VDD_K4") (pintype "passive"))
      (node (ref "U5") (pin "N10") (pinfunction "VDD_N10") (pintype "passive"))
      (node (ref "U5") (pin "N8") (pinfunction "VDD_N8") (pintype "passive"))
      (node (ref "U5") (pin "N9") (pinfunction "VDD_N9") (pintype "passive"))
      (node (ref "U5") (pin "P1") (pinfunction "VREF+_P1") (pintype "passive"))
      (node (ref "U5") (pin "R1") (pinfunction "VDDA_R1") (pintype "passive"))
      (node (ref "U7") (pin "5") (pinfunction "Vout_5") (pintype "passive"))
      (node (ref "X1") (pin "4") (pinfunction "VDD_4") (pintype "passive"))
    )
    (net (code "27") (name "5V") (class "Default")
      (node (ref "R12") (pin "1") (pinfunction "1_1") (pintype "passive"))
    )
    (net (code "28") (name "5V_USB_CHGR") (class "Default")
      (node (ref "C11") (pin "2") (pinfunction "2_2") (pintype "passive"))
      (node (ref "C2") (pin "2") (pinfunction "2_2") (pintype "passive"))
      (node (ref "CN1") (pin "1") (pinfunction "VBUS_1") (pintype "passive"))
      (node (ref "D1") (pin "1") (pinfunction "A_1") (pintype "passive"))
      (node (ref "R1") (pin "2") (pinfunction "2_2") (pintype "passive"))
      (node (ref "R6") (pin "2") (pinfunction "2_2") (pintype "passive"))
      (node (ref "U3") (pin "1") (pinfunction "IO1_1") (pintype "passive"))
      (node (ref "U4") (pin "5") (pinfunction "IN_5") (pintype "passive"))
    )
    (net (code "29") (name "5V_USB_STLK") (class "Default")
      (node (ref "C5") (pin "2") (pinfunction "2_2") (pintype "passive"))
      (node (ref "U4") (pin "1") (pinfunction "OUT_1") (pintype "passive"))
    )
    (net (code "30") (name "5V_VIN") (class "Default")
      (node (ref "D3") (pin "1") (pinfunction "A_1") (pintype "passive"))
    )
    (net (code "31") (name "E5V") (class "Default")
      (node (ref "D2") (pin "1") (pinfunction "A_1") (pintype "passive"))
    )
    (net (code "32") (name "GND") (class "Default")
      (node (ref "C1") (pin "1") (pinfunction "1_1") (pintype "passive"))
      (node (ref "C10") (pin "1") (pinfunction "1_1") (pintype "passive"))
      (node (ref "C11") (pin "1") (pinfunction "1_1") (pintype "passive"))
      (node (ref "C12") (pin "1") (pinfunction "1_1") (pintype "passive"))
      (node (ref "C13") (pin "1") (pinfunction "1_1") (pintype "passive"))
      (node (ref "C14") (pin "1") (pinfunction "1_1") (pintype "passive"))
      (node (ref "C15") (pin "1") (pinfunction "1_1") (pintype "passive"))
      (node (ref "C16") (pin "1") (pinfunction "1_1") (pintype "passive"))
      (node (ref "C17") (pin "1") (pinfunction "1_1") (pintype "passive"))
      (node (ref "C18") (pin "1") (pinfunction "1_1") (pintype "passive"))
      (node (ref "C19") (pin "1") (pinfunction "1_1") (pintype "passive"))
      (node (ref "C2") (pin "1") (pinfunction "1_1") (pintype "passive"))
      (node (ref "C20") (pin "1") (pinfunction "1_1") (pintype "passive"))
      (node (ref "C21") (pin "1") (pinfunction "1_1") (pintype "passive"))
      (node (ref "C22") (pin "1") (pinfunction "1_1") (pintype "passive"))
      (node (ref "C23") (pin "1") (pinfunction "1_1") (pintype "passive"))
      (node (ref "C24") (pin "1") (pinfunction "1_1") (pintype "passive"))
      (node (ref "C25") (pin "1") (pinfunction "1_1") (pintype "passive"))
      (node (ref "C26") (pin "1") (pinfunction "1_1") (pintype "passive"))
      (node (ref "C27") (pin "1") (pinfunction "1_1") (pintype "passive"))
      (node (ref "C28") (pin "1") (pinfunction "1_1") (pintype "passive"))
      (node (ref "C29") (pin "1") (pinfunction "1_1") (pintype "passive"))
      (node (ref "C3") (pin "1") (pinfunction "1_1") (pintype "passive"))
      (node (ref "C30") (pin "1") (pinfunction "1_1") (pintype "passive"))
      (node (ref "C31") (pin "1") (pinfunction "1_1") (pintype "passive"))
      (node (ref "C32") (pin "1") (pinfunction "1_1") (pintype "passive"))
      (node (ref "C33") (pin "1") (pinfunction "1_1") (pintype "passive"))
      (node (ref "C4") (pin "1") (pinfunction "1_1") (pintype "passive"))
      (node (ref "C5") (pin "1") (pinfunction "1_1") (pintype "passive"))
      (node (ref "C6") (pin "1") (pinfunction "1_1") (pintype "passive"))
      (node (ref "C7") (pin "1") (pinfunction "1_1") (pintype "passive"))
      (node (ref "C8") (pin "1") (pinfunction "1_1") (pintype "passive"))
      (node (ref "C9") (pin "1") (pinfunction "1_1") (pintype "passive"))
      (node (ref "CN1") (pin "10") (pinfunction "EXP_10") (pintype "passive"))
      (node (ref "CN1") (pin "11") (pinfunction "EXP_11") (pintype "passive"))
      (node (ref "CN1") (pin "5") (pinfunction "GND_5") (pintype "passive"))
      (node (ref "CN1") (pin "6") (pinfunction "Shield_6") (pintype "passive"))
      (node (ref "CN1") (pin "7") (pinfunction "Shield_7") (pintype "passive"))
      (node (ref "CN1") (pin "8") (pinfunction "Shield_8") (pintype "passive"))
      (node (ref "CN1") (pin "9") (pinfunction "Shield_9") (pintype "passive"))
      (node (ref "CN11") (pin "1") (pinfunction "COMMON_1") (pintype "passive"))
      (node (ref "CN11") (pin "2") (pinfunction "NO_2") (pintype "passive"))
      (node (ref "CN12") (pin "1") (pinfunction "COMMON_1") (pintype "passive"))
      (node (ref "CN12") (pin "2") (pinfunction "NO_2") (pintype "passive"))
      (node (ref "CN2") (pin "3") (pinfunction "3_3") (pintype "passive"))
      (node (ref "CN4") (pin "5") (pinfunction "5_5") (pintype "passive"))
      (node (ref "CN4") (pin "7") (pinfunction "7_7") (pintype "passive"))
      (node (ref "JP1") (pin "1") (pinfunction "COMMON_1") (pintype "passive"))
      (node (ref "LD1") (pin "1") (pinfunction "RED_cathode_1") (pintype "passive"))
      (node (ref "R11") (pin "1") (pinfunction "1_1") (pintype "passive"))
      (node (ref "R15") (pin "1") (pinfunction "1_1") (pintype "passive"))
      (node (ref "R16") (pin "2") (pinfunction "2_2") (pintype "passive"))
      (node (ref "R17") (pin "1") (pinfunction "1_1") (pintype "passive"))
      (node (ref "R21") (pin "1") (pinfunction "1_1") (pintype "passive"))
      (node (ref "R5") (pin "1") (pinfunction "1_1") (pintype "passive"))
      (node (ref "R8") (pin "2") (pinfunction "2_2") (pintype "passive"))
      (node (ref "U1") (pin "2") (pinfunction "GND_2") (pintype "passive"))
      (node (ref "U2") (pin "3") (pinfunction "GND_3") (pintype "passive"))
      (node (ref "U3") (pin "2") (pinfunction "GND_2") (pintype "passive"))
      (node (ref "U4") (pin "2") (pinfunction "GND_2") (pintype "passive"))
      (node (ref "U5") (pin "D5") (pinfunction "VSS_D5") (pintype "passive"))
      (node (ref "U5") (pin "D7") (pinfunction "VSS_D7") (pintype "passive"))
      (node (ref "U5") (pin "D8") (pinfunction "VSS_D8") (pintype "passive"))
      (node (ref "U5") (pin "D9") (pinfunction "VSS_D9") (pintype "passive"))
      (node (ref "U5") (pin "F10") (pinfunction "VSS_F10") (pintype "passive"))
      (node (ref "U5") (pin "F12") (pinfunction "VSS_F12") (pintype "passive"))
      (node (ref "U5") (pin "F2") (pinfunction "VSS_F2") (pintype "passive"))
      (node (ref "U5") (pin "F6") (pinfunction "VSS_F6") (pintype "passive"))
      (node (ref "U5") (pin "F7") (pinfunction "VSS_F7") (pintype "passive"))
      (node (ref "U5") (pin "F8") (pinfunction "VSS_F8") (pintype "passive"))
      (node (ref "U5") (pin "F9") (pinfunction "VSS_F9") (pintype "passive"))
      (node (ref "U5") (pin "G10") (pinfunction "VSS_G10") (pintype "passive"))
      (node (ref "U5") (pin "G12") (pinfunction "VSS_G12") (pintype "passive"))
      (node (ref "U5") (pin "G2") (pinfunction "VSS_G2") (pintype "passive"))
      (node (ref "U5") (pin "G6") (pinfunction "VSS_G6") (pintype "passive"))
      (node (ref "U5") (pin "G7") (pinfunction "VSS_G7") (pintype "passive"))
      (node (ref "U5") (pin "G8") (pinfunction "VSS_G8") (pintype "passive"))
      (node (ref "U5") (pin "G9") (pinfunction "VSS_G9") (pintype "passive"))
      (node (ref "U5") (pin "H10") (pinfunction "VSS_H10") (pintype "passive"))
      (node (ref "U5") (pin "H12") (pinfunction "VSS_H12") (pintype "passive"))
      (node (ref "U5") (pin "H6") (pinfunction "VSS_H6") (pintype "passive"))
      (node (ref "U5") (pin "H7") (pinfunction "VSS_H7") (pintype "passive"))
      (node (ref "U5") (pin "H8") (pinfunction "VSS_H8") (pintype "passive"))
      (node (ref "U5") (pin "H9") (pinfunction "VSS_H9") (pintype "passive"))
      (node (ref "U5") (pin "J10") (pinfunction "VSS_J10") (pintype "passive"))
      (node (ref "U5") (pin "J6") (pinfunction "VSS_J6") (pintype "passive"))
      (node (ref "U5") (pin "J7") (pinfunction "VSS_J7") (pintype "passive"))
      (node (ref "U5") (pin "J8") (pinfunction "VSS_J8") (pintype "passive"))
      (node (ref "U5") (pin "J9") (pinfunction "VSS_J9") (pintype "passive"))
      (node (ref "U5") (pin "K10") (pinfunction "VSS_K10") (pintype "passive"))
      (node (ref "U5") (pin "K6") (pinfunction "VSS_K6") (pintype "passive"))
      (node (ref "U5") (pin "K7") (pinfunction "VSS_K7") (pintype "passive"))
      (node (ref "U5") (pin "K8") (pinfunction "VSS_K8") (pintype "passive"))
      (node (ref "U5") (pin "K9") (pinfunction "VSS_K9") (pintype "passive"))
      (node (ref "U5") (pin "M1") (pinfunction "VSSA_M1") (pintype "passive"))
      (node (ref "U5") (pin "M8") (pinfunction "VSS_M8") (pintype "passive"))
      (node (ref "U5") (pin "M9") (pinfunction "VSS_M9") (pintype "passive"))
      (node (ref "U5") (pin "N1") (pinfunction "VREF-_N1") (pintype "passive"))
      (node (ref "U6") (pin "2") (pinfunction "GND_2") (pintype "passive"))
      (node (ref "U7") (pin "2") (pinfunction "GND_2") (pintype "passive"))
      (node (ref "U8") (pin "2") (pinfunction "GND_2") (pintype "passive"))
      (node (ref "X1") (pin "2") (pinfunction "GND_2") (pintype "passive"))
    )
    (net (code "33") (name "Net-(D1-K)") (class "Default")
      (node (ref "C19") (pin "2") (pinfunction "2_2") (pintype "passive"))
      (node (ref "C20") (pin "2") (pinfunction "2_2") (pintype "passive"))
      (node (ref "D1") (pin "2") (pinfunction "K_2") (pintype "passive"))
      (node (ref "D2") (pin "2") (pinfunction "K_2") (pintype "passive"))
      (node (ref "D3") (pin "2") (pinfunction "K_2") (pintype "passive"))
      (node (ref "U7") (pin "1") (pinfunction "Vin_1") (pintype "passive"))
      (node (ref "U7") (pin "3") (pinfunction "CE_3") (pintype "passive"))
    )
    (net (code "34") (name "Net-(JP1-NO)") (class "Default")
      (node (ref "C1") (pin "2") (pinfunction "2_2") (pintype "passive"))
      (node (ref "JP1") (pin "2") (pinfunction "NO_2") (pintype "passive"))
      (node (ref "U5") (pin "J1") (pinfunction "NRST_J1") (pintype "passive"))
    )
    (net (code "35") (name "Net-(JP3-NO)") (class "Default")
      (node (ref "JP3") (pin "2") (pinfunction "NO_2") (pintype "passive"))
      (node (ref "R18") (pin "1") (pinfunction "1_1") (pintype "passive"))
    )
    (net (code "36") (name "Net-(LD1-Red_anode)") (class "Default")
      (node (ref "LD1") (pin "2") (pinfunction "Red_anode_2") (pintype "passive"))
      (node (ref "R3") (pin "1") (pinfunction "1_1") (pintype "passive"))
    )
    (net (code "37") (name "Net-(LD1-YellowGreen_cathode)") (class "Default")
      (node (ref "LD1") (pin "3") (pinfunction "YellowGreen_cathode_3") (pintype "passive"))
      (node (ref "R2") (pin "1") (pinfunction "1_1") (pintype "passive"))
    )
    (net (code "38") (name "Net-(LD4-Pad1)") (class "Default")
      (node (ref "LD4") (pin "1") (pintype "passive"))
      (node (ref "R1") (pin "1") (pinfunction "1_1") (pintype "passive"))
    )
    (net (code "39") (name "Net-(U4-~{FAULT})") (class "Default")
      (node (ref "LD4") (pin "2") (pintype "passive"))
      (node (ref "R6") (pin "1") (pinfunction "1_1") (pintype "passive"))
      (node (ref "U4") (pin "3") (pinfunction "~{FAULT}_3") (pintype "passive"))
    )
    (net (code "40") (name "Net-(U5A-BOOT0)") (class "Default")
      (node (ref "R17") (pin "2") (pinfunction "2_2") (pintype "passive"))
      (node (ref "U5") (pin "D6") (pinfunction "BOOT0_D6") (pintype "passive"))
    )
    (net (code "41") (name "Net-(U5A-OSC_IN{slash}PH0)") (class "Default")
      (node (ref "R20") (pin "2") (pinfunction "2_2") (pintype "passive"))
      (node (ref "U5") (pin "G1") (pinfunction "OSC_IN/PH0_G1") (pintype "passive"))
    )
    (net (code "42") (name "Net-(U5A-PDR_ON)") (class "Default")
      (node (ref "R14") (pin "2") (pinfunction "2_2") (pintype "passive"))
      (node (ref "U5") (pin "C6") (pinfunction "PDR_ON_C6") (pintype "passive"))
    )
    (net (code "43") (name "Net-(U5A-REXT_OTGPHY)") (class "Default")
      (node (ref "R5") (pin "2") (pinfunction "2_2") (pintype "passive"))
      (node (ref "U5") (pin "J15") (pinfunction "REXT_OTGPHY_J15") (pintype "passive"))
    )
    (net (code "44") (name "Net-(U5A-STLK_MCO{slash}PA8)") (class "Default")
      (node (ref "R4") (pin "1") (pinfunction "1_1") (pintype "passive"))
      (node (ref "U5") (pin "F15") (pinfunction "STLK_MCO/PA8_F15") (pintype "passive"))
    )
    (net (code "45") (name "Net-(U5A-T_VCC_AIN{slash}PA0)") (class "Default")
      (node (ref "R16") (pin "1") (pinfunction "1_1") (pintype "passive"))
      (node (ref "R19") (pin "1") (pinfunction "1_1") (pintype "passive"))
      (node (ref "U5") (pin "N3") (pinfunction "T_VCC_AIN/PA0_N3") (pintype "passive"))
    )
    (net (code "46") (name "Net-(U5A-V12_OTGPHY)") (class "Default")
      (node (ref "C4") (pin "2") (pinfunction "2_2") (pintype "passive"))
      (node (ref "U5") (pin "J14") (pinfunction "V12_OTGPHY_J14") (pintype "passive"))
    )
    (net (code "47") (name "Net-(U5B-BYPASS-REG)") (class "Default")
      (node (ref "R21") (pin "2") (pinfunction "2_2") (pintype "passive"))
      (node (ref "U5") (pin "L4") (pinfunction "BYPASS-REG_L4") (pintype "passive"))
    )
    (net (code "48") (name "Net-(U5B-VCAP1)") (class "Default")
      (node (ref "C12") (pin "2") (pinfunction "2_2") (pintype "passive"))
      (node (ref "U5") (pin "M10") (pinfunction "VCAP1_M10") (pintype "passive"))
    )
    (net (code "49") (name "Net-(U5B-VCAP2)") (class "Default")
      (node (ref "C10") (pin "2") (pinfunction "2_2") (pintype "passive"))
      (node (ref "U5") (pin "F13") (pinfunction "VCAP2_F13") (pintype "passive"))
    )
    (net (code "50") (name "Net-(U7-BYPASS)") (class "Default")
      (node (ref "C30") (pin "2") (pinfunction "2_2") (pintype "passive"))
      (node (ref "U7") (pin "4") (pinfunction "BYPASS_4") (pintype "passive"))
    )
    (net (code "51") (name "Net-(X1-EN)") (class "Default")
      (node (ref "R24") (pin "2") (pinfunction "2_2") (pintype "passive"))
      (node (ref "X1") (pin "1") (pinfunction "EN_1") (pintype "passive"))
    )
    (net (code "52") (name "Net-(X1-OUT)") (class "Default")
      (node (ref "R20") (pin "1") (pinfunction "1_1") (pintype "passive"))
      (node (ref "X1") (pin "3") (pinfunction "OUT_3") (pintype "passive"))
    )
    (net (code "53") (name "unconnected-(CN1-ID-Pad4)") (class "Default")
      (node (ref "CN1") (pin "4") (pinfunction "ID_4") (pintype "passive+no_connect"))
    )
    (net (code "54") (name "unconnected-(CN4-Pad1)") (class "Default")
      (node (ref "CN4") (pin "1") (pinfunction "1_1") (pintype "passive+no_connect"))
    )
    (net (code "55") (name "unconnected-(CN4-Pad2)") (class "Default")
      (node (ref "CN4") (pin "2") (pinfunction "2_2") (pintype "passive+no_connect"))
    )
    (net (code "56") (name "unconnected-(CN4-Pad9)") (class "Default")
      (node (ref "CN4") (pin "9") (pinfunction "9_9") (pintype "passive+no_connect"))
    )
    (net (code "57") (name "unconnected-(U2-NC-Pad4)") (class "Default")
      (node (ref "U2") (pin "4") (pinfunction "NC_4") (pintype "passive+no_connect"))
    )
    (net (code "58") (name "unconnected-(U5A-HW_TYP_0{slash}PI4-PadD4)") (class "Default")
      (node (ref "U5") (pin "D4") (pinfunction "HW_TYP_0/PI4_D4") (pintype "passive+no_connect"))
    )
    (net (code "59") (name "unconnected-(U5A-HW_TYP_1{slash}PI5-PadC4)") (class "Default")
      (node (ref "U5") (pin "C4") (pinfunction "HW_TYP_1/PI5_C4") (pintype "passive+no_connect"))
    )
    (net (code "60") (name "unconnected-(U5A-OSC_OUT{slash}PH1-PadH1)") (class "Default")
      (node (ref "U5") (pin "H1") (pinfunction "OSC_OUT/PH1_H1") (pintype "passive+no_connect"))
    )
    (net (code "61") (name "unconnected-(U5A-T_SW_DIR{slash}PA7-PadR3)") (class "Default")
      (node (ref "U5") (pin "R3") (pinfunction "T_SW_DIR/PA7_R3") (pintype "passive+no_connect"))
    )
  )
)
